# sensor_board.net
KiCad netlist of a schematic drawn in EAGLE
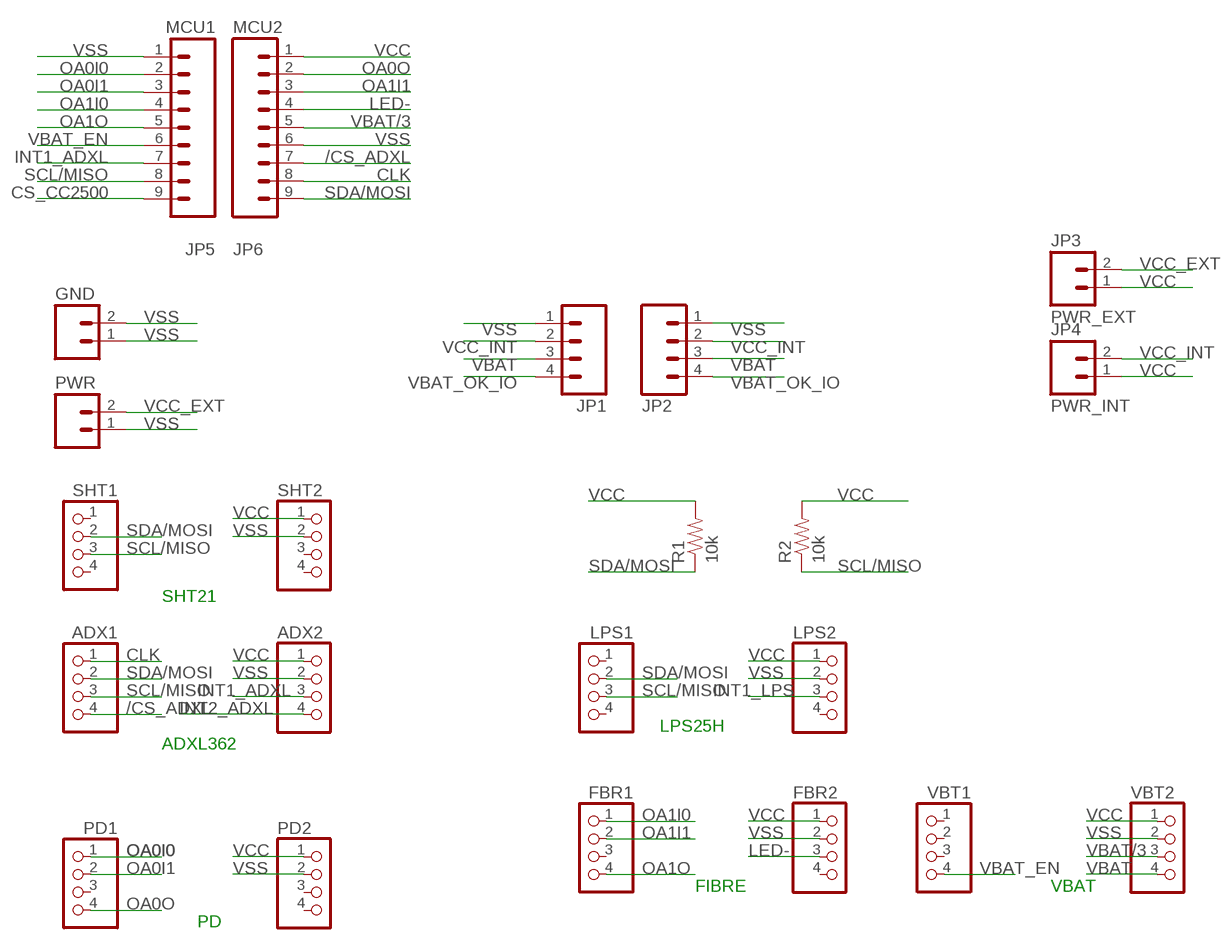
[diagram p0: schematic, sheet 1]

(export (version "E")
  (design (tool "Eeschema 10.0.6"))
  (components
    (comp (ref "ADX1")
      (value "PINHD-1X4")
      (footprint "eagle-import:1X04")
      (libsource (lib "eagle-import") (part "PINHD-1X4"))
    )
    (comp (ref "ADX2")
      (value "PINHD-1X4")
      (footprint "eagle-import:1X04")
      (libsource (lib "eagle-import") (part "PINHD-1X4"))
    )
    (comp (ref "FBR1")
      (value "PINHD-1X4")
      (footprint "eagle-import:1X04")
      (libsource (lib "eagle-import") (part "PINHD-1X4"))
    )
    (comp (ref "FBR2")
      (value "PINHD-1X4")
      (footprint "eagle-import:1X04")
      (libsource (lib "eagle-import") (part "PINHD-1X4"))
    )
    (comp (ref "GND")
      (value "M02PTH")
      (footprint "eagle-import:1X02")
      (libsource (lib "eagle-import") (part "M02PTH"))
    )
    (comp (ref "JP1")
      (value "M04PTH")
      (footprint "eagle-import:1X04")
      (libsource (lib "eagle-import") (part "M04PTH"))
    )
    (comp (ref "JP2")
      (value "M04PTH")
      (footprint "eagle-import:1X04")
      (libsource (lib "eagle-import") (part "M04PTH"))
    )
    (comp (ref "JP3")
      (value "PWR_EXT")
      (footprint "eagle-import:1X02")
      (libsource (lib "eagle-import") (part "M02PTH"))
    )
    (comp (ref "JP4")
      (value "PWR_INT")
      (footprint "eagle-import:1X02")
      (libsource (lib "eagle-import") (part "M02PTH"))
    )
    (comp (ref "JP5")
      (value "MCU1")
      (footprint "eagle-import:1X09")
      (libsource (lib "eagle-import") (part "M09"))
    )
    (comp (ref "JP6")
      (value "MCU2")
      (footprint "eagle-import:1X09")
      (libsource (lib "eagle-import") (part "passive_components_M09"))
    )
    (comp (ref "LPS1")
      (value "PINHD-1X4")
      (footprint "eagle-import:1X04")
      (libsource (lib "eagle-import") (part "PINHD-1X4"))
    )
    (comp (ref "LPS2")
      (value "PINHD-1X4")
      (footprint "eagle-import:1X04")
      (libsource (lib "eagle-import") (part "PINHD-1X4"))
    )
    (comp (ref "PD1")
      (value "PINHD-1X4")
      (footprint "eagle-import:1X04")
      (libsource (lib "eagle-import") (part "PINHD-1X4"))
    )
    (comp (ref "PD2")
      (value "PINHD-1X4")
      (footprint "eagle-import:1X04")
      (libsource (lib "eagle-import") (part "PINHD-1X4"))
    )
    (comp (ref "PWR")
      (value "M02PTH")
      (footprint "eagle-import:1X02")
      (libsource (lib "eagle-import") (part "M02PTH"))
    )
    (comp (ref "R1")
      (value "10k")
      (footprint "eagle-import:AXIAL-0.3")
      (libsource (lib "eagle-import") (part "10KOHM-1/4W5%(PTH)"))
    )
    (comp (ref "R2")
      (value "10k")
      (footprint "eagle-import:AXIAL-0.3")
      (libsource (lib "eagle-import") (part "10KOHM-1/4W5%(PTH)"))
    )
    (comp (ref "SHT1")
      (value "PINHD-1X4")
      (footprint "eagle-import:1X04")
      (libsource (lib "eagle-import") (part "PINHD-1X4"))
    )
    (comp (ref "SHT2")
      (value "PINHD-1X4")
      (footprint "eagle-import:1X04")
      (libsource (lib "eagle-import") (part "PINHD-1X4"))
    )
    (comp (ref "VBT1")
      (value "PINHD-1X4")
      (footprint "eagle-import:1X04")
      (libsource (lib "eagle-import") (part "PINHD-1X4"))
    )
    (comp (ref "VBT2")
      (value "PINHD-1X4")
      (footprint "eagle-import:1X04")
      (libsource (lib "eagle-import") (part "PINHD-1X4"))
    )
  )
  (nets
    (net (code "1") (name "/CLK") (class "Default")
      (node (ref "ADX1") (pin "1") (pinfunction "1_1") (pintype "passive"))
      (node (ref "JP6") (pin "8") (pinfunction "8_8") (pintype "passive"))
    )
    (net (code "2") (name "/CS_CC2500") (class "Default")
      (node (ref "JP5") (pin "9") (pinfunction "9_9") (pintype "passive"))
    )
    (net (code "3") (name "/INT1_ADXL") (class "Default")
      (node (ref "ADX2") (pin "3") (pinfunction "3_3") (pintype "passive"))
      (node (ref "JP5") (pin "7") (pinfunction "7_7") (pintype "passive"))
    )
    (net (code "4") (name "/INT1_LPS") (class "Default")
      (node (ref "LPS2") (pin "3") (pinfunction "3_3") (pintype "passive"))
    )
    (net (code "5") (name "/INT2_ADXL") (class "Default")
      (node (ref "ADX2") (pin "4") (pinfunction "4_4") (pintype "passive"))
    )
    (net (code "6") (name "/LED-") (class "Default")
      (node (ref "FBR2") (pin "3") (pinfunction "3_3") (pintype "passive"))
      (node (ref "JP6") (pin "4") (pinfunction "4_4") (pintype "passive"))
    )
    (net (code "7") (name "/OA0I0") (class "Default")
      (node (ref "JP5") (pin "2") (pinfunction "2_2") (pintype "passive"))
      (node (ref "PD1") (pin "1") (pinfunction "1_1") (pintype "passive"))
    )
    (net (code "8") (name "/OA0I1") (class "Default")
      (node (ref "JP5") (pin "3") (pinfunction "3_3") (pintype "passive"))
      (node (ref "PD1") (pin "2") (pinfunction "2_2") (pintype "passive"))
    )
    (net (code "9") (name "/OA0O") (class "Default")
      (node (ref "JP6") (pin "2") (pinfunction "2_2") (pintype "passive"))
      (node (ref "PD1") (pin "4") (pinfunction "4_4") (pintype "passive"))
    )
    (net (code "10") (name "/OA1I0") (class "Default")
      (node (ref "FBR1") (pin "1") (pinfunction "1_1") (pintype "passive"))
      (node (ref "JP5") (pin "4") (pinfunction "4_4") (pintype "passive"))
    )
    (net (code "11") (name "/OA1I1") (class "Default")
      (node (ref "FBR1") (pin "2") (pinfunction "2_2") (pintype "passive"))
      (node (ref "JP6") (pin "3") (pinfunction "3_3") (pintype "passive"))
    )
    (net (code "12") (name "/OA1O") (class "Default")
      (node (ref "FBR1") (pin "4") (pinfunction "4_4") (pintype "passive"))
      (node (ref "JP5") (pin "5") (pinfunction "5_5") (pintype "passive"))
    )
    (net (code "13") (name "/SCL{slash}MISO") (class "Default")
      (node (ref "ADX1") (pin "3") (pinfunction "3_3") (pintype "passive"))
      (node (ref "JP5") (pin "8") (pinfunction "8_8") (pintype "passive"))
      (node (ref "LPS1") (pin "3") (pinfunction "3_3") (pintype "passive"))
      (node (ref "R2") (pin "P$1") (pinfunction "1_P$1") (pintype "passive"))
      (node (ref "SHT1") (pin "3") (pinfunction "3_3") (pintype "passive"))
    )
    (net (code "14") (name "/SDA{slash}MOSI") (class "Default")
      (node (ref "ADX1") (pin "2") (pinfunction "2_2") (pintype "passive"))
      (node (ref "JP6") (pin "9") (pinfunction "9_9") (pintype "passive"))
      (node (ref "LPS1") (pin "2") (pinfunction "2_2") (pintype "passive"))
      (node (ref "R1") (pin "P$1") (pinfunction "1_P$1") (pintype "passive"))
      (node (ref "SHT1") (pin "2") (pinfunction "2_2") (pintype "passive"))
    )
    (net (code "15") (name "/VBAT") (class "Default")
      (node (ref "JP1") (pin "3") (pinfunction "3_3") (pintype "passive"))
      (node (ref "JP2") (pin "3") (pinfunction "3_3") (pintype "passive"))
      (node (ref "VBT2") (pin "4") (pinfunction "4_4") (pintype "passive"))
    )
    (net (code "16") (name "/VBAT_EN") (class "Default")
      (node (ref "JP5") (pin "6") (pinfunction "6_6") (pintype "passive"))
      (node (ref "VBT1") (pin "4") (pinfunction "4_4") (pintype "passive"))
    )
    (net (code "17") (name "/VBAT_OK_IO") (class "Default")
      (node (ref "JP1") (pin "4") (pinfunction "4_4") (pintype "passive"))
      (node (ref "JP2") (pin "4") (pinfunction "4_4") (pintype "passive"))
    )
    (net (code "18") (name "/VBAT{slash}3") (class "Default")
      (node (ref "JP6") (pin "5") (pinfunction "5_5") (pintype "passive"))
      (node (ref "VBT2") (pin "3") (pinfunction "3_3") (pintype "passive"))
    )
    (net (code "19") (name "/VCC") (class "Default")
      (node (ref "ADX2") (pin "1") (pinfunction "1_1") (pintype "passive"))
      (node (ref "FBR2") (pin "1") (pinfunction "1_1") (pintype "passive"))
      (node (ref "JP3") (pin "1") (pinfunction "1_1") (pintype "passive"))
      (node (ref "JP4") (pin "1") (pinfunction "1_1") (pintype "passive"))
      (node (ref "JP6") (pin "1") (pinfunction "1_1") (pintype "passive"))
      (node (ref "LPS2") (pin "1") (pinfunction "1_1") (pintype "passive"))
      (node (ref "PD2") (pin "1") (pinfunction "1_1") (pintype "passive"))
      (node (ref "R1") (pin "P$2") (pinfunction "2_P$2") (pintype "passive"))
      (node (ref "R2") (pin "P$2") (pinfunction "2_P$2") (pintype "passive"))
      (node (ref "SHT2") (pin "1") (pinfunction "1_1") (pintype "passive"))
      (node (ref "VBT2") (pin "1") (pinfunction "1_1") (pintype "passive"))
    )
    (net (code "20") (name "/VCC_EXT") (class "Default")
      (node (ref "JP3") (pin "2") (pinfunction "2_2") (pintype "passive"))
      (node (ref "PWR") (pin "2") (pinfunction "2_2") (pintype "passive"))
    )
    (net (code "21") (name "/VCC_INT") (class "Default")
      (node (ref "JP1") (pin "2") (pinfunction "2_2") (pintype "passive"))
      (node (ref "JP2") (pin "2") (pinfunction "2_2") (pintype "passive"))
      (node (ref "JP4") (pin "2") (pinfunction "2_2") (pintype "passive"))
    )
    (net (code "22") (name "/VSS") (class "Default")
      (node (ref "ADX2") (pin "2") (pinfunction "2_2") (pintype "passive"))
      (node (ref "FBR2") (pin "2") (pinfunction "2_2") (pintype "passive"))
      (node (ref "GND") (pin "1") (pinfunction "1_1") (pintype "passive"))
      (node (ref "GND") (pin "2") (pinfunction "2_2") (pintype "passive"))
      (node (ref "JP1") (pin "1") (pinfunction "1_1") (pintype "passive"))
      (node (ref "JP2") (pin "1") (pinfunction "1_1") (pintype "passive"))
      (node (ref "JP5") (pin "1") (pinfunction "1_1") (pintype "passive"))
      (node (ref "JP6") (pin "6") (pinfunction "6_6") (pintype "passive"))
      (node (ref "LPS2") (pin "2") (pinfunction "2_2") (pintype "passive"))
      (node (ref "PD2") (pin "2") (pinfunction "2_2") (pintype "passive"))
      (node (ref "PWR") (pin "1") (pinfunction "1_1") (pintype "passive"))
      (node (ref "SHT2") (pin "2") (pinfunction "2_2") (pintype "passive"))
      (node (ref "VBT2") (pin "2") (pinfunction "2_2") (pintype "passive"))
    )
    (net (code "23") (name "/{slash}CS_ADXL") (class "Default")
      (node (ref "ADX1") (pin "4") (pinfunction "4_4") (pintype "passive"))
      (node (ref "JP6") (pin "7") (pinfunction "7_7") (pintype "passive"))
    )
    (net (code "24") (name "unconnected-(FBR1-Pad3)") (class "Default")
      (node (ref "FBR1") (pin "3") (pinfunction "3_3") (pintype "passive"))
    )
    (net (code "25") (name "unconnected-(FBR2-Pad4)") (class "Default")
      (node (ref "FBR2") (pin "4") (pinfunction "4_4") (pintype "passive"))
    )
    (net (code "26") (name "unconnected-(LPS1-Pad1)") (class "Default")
      (node (ref "LPS1") (pin "1") (pinfunction "1_1") (pintype "passive"))
    )
    (net (code "27") (name "unconnected-(LPS1-Pad4)") (class "Default")
      (node (ref "LPS1") (pin "4") (pinfunction "4_4") (pintype "passive"))
    )
    (net (code "28") (name "unconnected-(LPS2-Pad4)") (class "Default")
      (node (ref "LPS2") (pin "4") (pinfunction "4_4") (pintype "passive"))
    )
    (net (code "29") (name "unconnected-(PD1-Pad3)") (class "Default")
      (node (ref "PD1") (pin "3") (pinfunction "3_3") (pintype "passive"))
    )
    (net (code "30") (name "unconnected-(PD2-Pad3)") (class "Default")
      (node (ref "PD2") (pin "3") (pinfunction "3_3") (pintype "passive"))
    )
    (net (code "31") (name "unconnected-(PD2-Pad4)") (class "Default")
      (node (ref "PD2") (pin "4") (pinfunction "4_4") (pintype "passive"))
    )
    (net (code "32") (name "unconnected-(SHT1-Pad1)") (class "Default")
      (node (ref "SHT1") (pin "1") (pinfunction "1_1") (pintype "passive"))
    )
    (net (code "33") (name "unconnected-(SHT1-Pad4)") (class "Default")
      (node (ref "SHT1") (pin "4") (pinfunction "4_4") (pintype "passive"))
    )
    (net (code "34") (name "unconnected-(SHT2-Pad3)") (class "Default")
      (node (ref "SHT2") (pin "3") (pinfunction "3_3") (pintype "passive"))
    )
    (net (code "35") (name "unconnected-(SHT2-Pad4)") (class "Default")
      (node (ref "SHT2") (pin "4") (pinfunction "4_4") (pintype "passive"))
    )
    (net (code "36") (name "unconnected-(VBT1-Pad1)") (class "Default")
      (node (ref "VBT1") (pin "1") (pinfunction "1_1") (pintype "passive"))
    )
    (net (code "37") (name "unconnected-(VBT1-Pad2)") (class "Default")
      (node (ref "VBT1") (pin "2") (pinfunction "2_2") (pintype "passive"))
    )
    (net (code "38") (name "unconnected-(VBT1-Pad3)") (class "Default")
      (node (ref "VBT1") (pin "3") (pinfunction "3_3") (pintype "passive"))
    )
  )
)
